# remoteReceive.net
KiCad netlist of a schematic drawn in EAGLE
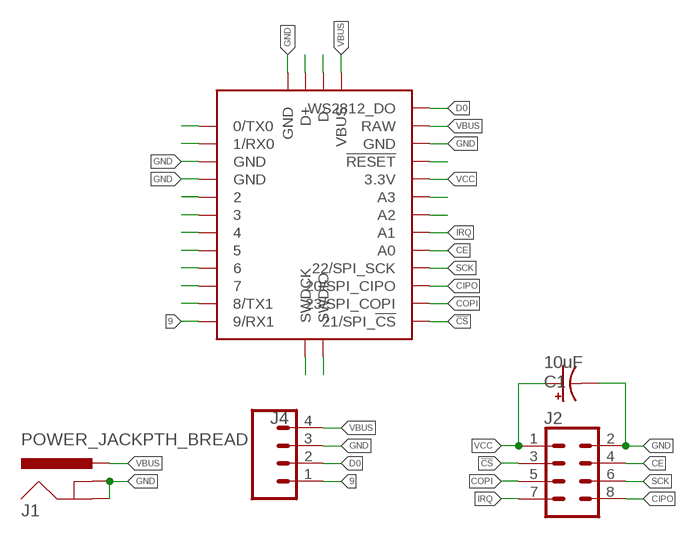
[diagram p0: schematic, sheet 1]

(export (version "E")
  (design (tool "Eeschema 10.0.6"))
  (components
    (comp (ref "C1")
      (value "10uF")
      (footprint "eagle-import:CPOL-RADIAL-2.5MM-5MM-KIT")
      (libsource (lib "eagle-import") (part "10UF-POLAR-RADIAL-2.5MM-KIT-25V-20%"))
    )
    (comp (ref "J1")
      (value "POWER_JACKPTH_BREAD")
      (footprint "eagle-import:POWER_JACK_PTH_BREAD")
      (libsource (lib "eagle-import") (part "POWER_JACKPTH_BREAD"))
    )
    (comp (ref "J2")
      (value "CONN_04X2")
      (footprint "eagle-import:2X4")
      (libsource (lib "eagle-import") (part "CONN_04X2"))
    )
    (comp (ref "J4")
      (value "CONN_04POLAR")
      (footprint "eagle-import:MOLEX-1X4")
      (libsource (lib "eagle-import") (part "CONN_04POLAR"))
    )
    (comp (ref "U$1")
      (value "SF17717_PROMICRORP2040_BREAKOUT")
      (footprint "eagle-import:SF17717_PROMICRORP2040_BREAKOUT")
      (libsource (lib "eagle-import") (part "SF17717_PROMICRORP2040_BREAKOUT"))
    )
  )
  (nets
    (net (code "1") (name "/~{CS}") (class "Default")
      (node (ref "J2") (pin "3") (pinfunction "3_3") (pintype "passive"))
      (node (ref "U$1") (pin "12R") (pinfunction "21/SPI_~{CS}_12R") (pintype "bidirectional"))
      (node (ref "U$1") (pin "12R_PADB") (pinfunction "21/SPI_~{CS}_12R_PADB") (pintype "bidirectional"))
      (node (ref "U$1") (pin "12R_PADT") (pinfunction "21/SPI_~{CS}_12R_PADT") (pintype "bidirectional"))
    )
    (net (code "2") (name "9") (class "Default")
      (node (ref "J4") (pin "1") (pinfunction "1_1") (pintype "passive"))
      (node (ref "U$1") (pin "01L") (pinfunction "9/RX1_01L") (pintype "bidirectional"))
      (node (ref "U$1") (pin "01L_PADB") (pinfunction "9/RX1_01L_PADB") (pintype "bidirectional"))
      (node (ref "U$1") (pin "01L_PADT") (pinfunction "9/RX1_01L_PADT") (pintype "bidirectional"))
    )
    (net (code "3") (name "CE") (class "Default")
      (node (ref "J2") (pin "4") (pinfunction "4_4") (pintype "passive"))
      (node (ref "U$1") (pin "08R") (pinfunction "A0_08R") (pintype "bidirectional"))
      (node (ref "U$1") (pin "08R_PADB") (pinfunction "A0_08R_PADB") (pintype "bidirectional"))
      (node (ref "U$1") (pin "08R_PADT") (pinfunction "A0_08R_PADT") (pintype "bidirectional"))
    )
    (net (code "4") (name "CIPO") (class "Default")
      (node (ref "J2") (pin "8") (pinfunction "8_8") (pintype "passive"))
      (node (ref "U$1") (pin "10R") (pinfunction "20/SPI_CIPO_10R") (pintype "bidirectional"))
      (node (ref "U$1") (pin "10R_PADB") (pinfunction "20/SPI_CIPO_10R_PADB") (pintype "bidirectional"))
      (node (ref "U$1") (pin "10R_PADT") (pinfunction "20/SPI_CIPO_10R_PADT") (pintype "bidirectional"))
    )
    (net (code "5") (name "COPI") (class "Default")
      (node (ref "J2") (pin "5") (pinfunction "5_5") (pintype "passive"))
      (node (ref "U$1") (pin "11R") (pinfunction "23/SPI_COPI_11R") (pintype "bidirectional"))
      (node (ref "U$1") (pin "11R_PADB") (pinfunction "23/SPI_COPI_11R_PADB") (pintype "bidirectional"))
      (node (ref "U$1") (pin "11R_PADT") (pinfunction "23/SPI_COPI_11R_PADT") (pintype "bidirectional"))
    )
    (net (code "6") (name "D0") (class "Default")
      (node (ref "J4") (pin "2") (pinfunction "2_2") (pintype "passive"))
      (node (ref "U$1") (pin "D0_B") (pinfunction "WS2812_DO_D0_B") (pintype "output"))
      (node (ref "U$1") (pin "D0_T") (pinfunction "WS2812_DO_D0_T") (pintype "output"))
    )
    (net (code "7") (name "GND") (class "Default")
      (node (ref "C1") (pin "2") (pinfunction "-_2") (pintype "passive"))
      (node (ref "J1") (pin "GND") (pinfunction "GND_GND") (pintype "bidirectional"))
      (node (ref "J1") (pin "GNDBREAK") (pinfunction "GNDBREAK_GNDBREAK") (pintype "bidirectional"))
      (node (ref "J2") (pin "2") (pinfunction "2_2") (pintype "passive"))
      (node (ref "J4") (pin "3") (pinfunction "3_3") (pintype "passive"))
      (node (ref "U$1") (pin "02R") (pinfunction "GND_02R") (pintype "power_in"))
      (node (ref "U$1") (pin "02R_PADB") (pinfunction "GND_02R_PADB") (pintype "power_in"))
      (node (ref "U$1") (pin "02R_PADT") (pinfunction "GND_02R_PADT") (pintype "power_in"))
      (node (ref "U$1") (pin "09L") (pinfunction "GND_09L") (pintype "power_in"))
      (node (ref "U$1") (pin "09L_PADB") (pinfunction "GND_09L_PADB") (pintype "power_in"))
      (node (ref "U$1") (pin "09L_PADT") (pinfunction "GND_09L_PADT") (pintype "power_in"))
      (node (ref "U$1") (pin "10L") (pinfunction "GND_10L") (pintype "power_in"))
      (node (ref "U$1") (pin "10L_PADB") (pinfunction "GND_10L_PADB") (pintype "power_in"))
      (node (ref "U$1") (pin "10L_PADT") (pinfunction "GND_10L_PADT") (pintype "power_in"))
      (node (ref "U$1") (pin "GND_B") (pinfunction "GND_GND_B") (pintype "power_in"))
      (node (ref "U$1") (pin "GND_T") (pinfunction "GND_GND_T") (pintype "power_in"))
    )
    (net (code "8") (name "IRQ") (class "Default")
      (node (ref "J2") (pin "7") (pinfunction "7_7") (pintype "passive"))
      (node (ref "U$1") (pin "07R") (pinfunction "A1_07R") (pintype "bidirectional"))
      (node (ref "U$1") (pin "07R_PADB") (pinfunction "A1_07R_PADB") (pintype "bidirectional"))
      (node (ref "U$1") (pin "07R_PADT") (pinfunction "A1_07R_PADT") (pintype "bidirectional"))
    )
    (net (code "9") (name "Net-(U$1-0{slash}TX0-Pad12L)") (class "Default")
      (node (ref "U$1") (pin "12L") (pinfunction "0/TX0_12L") (pintype "bidirectional"))
      (node (ref "U$1") (pin "12L_PADB") (pinfunction "0/TX0_12L_PADB") (pintype "bidirectional"))
      (node (ref "U$1") (pin "12L_PADT") (pinfunction "0/TX0_12L_PADT") (pintype "bidirectional"))
    )
    (net (code "10") (name "Net-(U$1-1{slash}RX0-Pad11L)") (class "Default")
      (node (ref "U$1") (pin "11L") (pinfunction "1/RX0_11L") (pintype "bidirectional"))
      (node (ref "U$1") (pin "11L_PADB") (pinfunction "1/RX0_11L_PADB") (pintype "bidirectional"))
      (node (ref "U$1") (pin "11L_PADT") (pinfunction "1/RX0_11L_PADT") (pintype "bidirectional"))
    )
    (net (code "11") (name "Net-(U$1-2-Pad08L)") (class "Default")
      (node (ref "U$1") (pin "08L") (pinfunction "2_08L") (pintype "bidirectional"))
      (node (ref "U$1") (pin "08L_PADB") (pinfunction "2_08L_PADB") (pintype "bidirectional"))
      (node (ref "U$1") (pin "08L_PADT") (pinfunction "2_08L_PADT") (pintype "bidirectional"))
    )
    (net (code "12") (name "Net-(U$1-3-Pad07L)") (class "Default")
      (node (ref "U$1") (pin "07L") (pinfunction "3_07L") (pintype "bidirectional"))
      (node (ref "U$1") (pin "07L_PADB") (pinfunction "3_07L_PADB") (pintype "bidirectional"))
      (node (ref "U$1") (pin "07L_PADT") (pinfunction "3_07L_PADT") (pintype "bidirectional"))
    )
    (net (code "13") (name "Net-(U$1-4-Pad06L)") (class "Default")
      (node (ref "U$1") (pin "06L") (pinfunction "4_06L") (pintype "bidirectional"))
      (node (ref "U$1") (pin "06L_PADB") (pinfunction "4_06L_PADB") (pintype "bidirectional"))
      (node (ref "U$1") (pin "06L_PADT") (pinfunction "4_06L_PADT") (pintype "bidirectional"))
    )
    (net (code "14") (name "Net-(U$1-5-Pad05L)") (class "Default")
      (node (ref "U$1") (pin "05L") (pinfunction "5_05L") (pintype "bidirectional"))
      (node (ref "U$1") (pin "05L_PADB") (pinfunction "5_05L_PADB") (pintype "bidirectional"))
      (node (ref "U$1") (pin "05L_PADT") (pinfunction "5_05L_PADT") (pintype "bidirectional"))
    )
    (net (code "15") (name "Net-(U$1-6-Pad04L)") (class "Default")
      (node (ref "U$1") (pin "04L") (pinfunction "6_04L") (pintype "bidirectional"))
      (node (ref "U$1") (pin "04L_PADB") (pinfunction "6_04L_PADB") (pintype "bidirectional"))
      (node (ref "U$1") (pin "04L_PADT") (pinfunction "6_04L_PADT") (pintype "bidirectional"))
    )
    (net (code "16") (name "Net-(U$1-7-Pad03L)") (class "Default")
      (node (ref "U$1") (pin "03L") (pinfunction "7_03L") (pintype "bidirectional"))
      (node (ref "U$1") (pin "03L_PADB") (pinfunction "7_03L_PADB") (pintype "bidirectional"))
      (node (ref "U$1") (pin "03L_PADT") (pinfunction "7_03L_PADT") (pintype "bidirectional"))
    )
    (net (code "17") (name "Net-(U$1-8{slash}TX1-Pad02L)") (class "Default")
      (node (ref "U$1") (pin "02L") (pinfunction "8/TX1_02L") (pintype "bidirectional"))
      (node (ref "U$1") (pin "02L_PADB") (pinfunction "8/TX1_02L_PADB") (pintype "bidirectional"))
      (node (ref "U$1") (pin "02L_PADT") (pinfunction "8/TX1_02L_PADT") (pintype "bidirectional"))
    )
    (net (code "18") (name "Net-(U$1-A2-Pad06R)") (class "Default")
      (node (ref "U$1") (pin "06R") (pinfunction "A2_06R") (pintype "bidirectional"))
      (node (ref "U$1") (pin "06R_PADB") (pinfunction "A2_06R_PADB") (pintype "bidirectional"))
      (node (ref "U$1") (pin "06R_PADT") (pinfunction "A2_06R_PADT") (pintype "bidirectional"))
    )
    (net (code "19") (name "Net-(U$1-A3-Pad05R)") (class "Default")
      (node (ref "U$1") (pin "05R") (pinfunction "A3_05R") (pintype "bidirectional"))
      (node (ref "U$1") (pin "05R_PADB") (pinfunction "A3_05R_PADB") (pintype "bidirectional"))
      (node (ref "U$1") (pin "05R_PADT") (pinfunction "A3_05R_PADT") (pintype "bidirectional"))
    )
    (net (code "20") (name "Net-(U$1-D+-PadD+_B)") (class "Default")
      (node (ref "U$1") (pin "D+_B") (pinfunction "D+_D+_B") (pintype "bidirectional"))
      (node (ref "U$1") (pin "D+_T") (pinfunction "D+_D+_T") (pintype "bidirectional"))
    )
    (net (code "21") (name "Net-(U$1-D--PadD-_B)") (class "Default")
      (node (ref "U$1") (pin "D-_B") (pinfunction "D-_D-_B") (pintype "bidirectional"))
      (node (ref "U$1") (pin "D-_T") (pinfunction "D-_D-_T") (pintype "bidirectional"))
    )
    (net (code "22") (name "Net-(U$1-SWDCK-PadSWDCK_B)") (class "Default")
      (node (ref "U$1") (pin "SWDCK_B") (pinfunction "SWDCK_SWDCK_B") (pintype "bidirectional"))
      (node (ref "U$1") (pin "SWDCK_T") (pinfunction "SWDCK_SWDCK_T") (pintype "bidirectional"))
    )
    (net (code "23") (name "Net-(U$1-SWDIO-PadSWDIO_B)") (class "Default")
      (node (ref "U$1") (pin "SWDIO_B") (pinfunction "SWDIO_SWDIO_B") (pintype "bidirectional"))
      (node (ref "U$1") (pin "SWDIO_T") (pinfunction "SWDIO_SWDIO_T") (pintype "bidirectional"))
    )
    (net (code "24") (name "Net-(U$1-~{RESET}-Pad03R)") (class "Default")
      (node (ref "U$1") (pin "03R") (pinfunction "~{RESET}_03R") (pintype "power_in"))
      (node (ref "U$1") (pin "03R_PADB") (pinfunction "~{RESET}_03R_PADB") (pintype "power_in"))
      (node (ref "U$1") (pin "03R_PADT") (pinfunction "~{RESET}_03R_PADT") (pintype "power_in"))
    )
    (net (code "25") (name "SCK") (class "Default")
      (node (ref "J2") (pin "6") (pinfunction "6_6") (pintype "passive"))
      (node (ref "U$1") (pin "09R") (pinfunction "22/SPI_SCK_09R") (pintype "bidirectional"))
      (node (ref "U$1") (pin "09R_PADB") (pinfunction "22/SPI_SCK_09R_PADB") (pintype "bidirectional"))
      (node (ref "U$1") (pin "09R_PADT") (pinfunction "22/SPI_SCK_09R_PADT") (pintype "bidirectional"))
    )
    (net (code "26") (name "VBUS") (class "Default")
      (node (ref "J1") (pin "PWR") (pinfunction "PWR_PWR") (pintype "bidirectional"))
      (node (ref "J4") (pin "4") (pinfunction "4_4") (pintype "passive"))
      (node (ref "U$1") (pin "01R") (pinfunction "RAW_01R") (pintype "power_in"))
      (node (ref "U$1") (pin "01R_PADB") (pinfunction "RAW_01R_PADB") (pintype "power_in"))
      (node (ref "U$1") (pin "01R_PADT") (pinfunction "RAW_01R_PADT") (pintype "power_in"))
      (node (ref "U$1") (pin "VBUS_B") (pinfunction "VBUS_VBUS_B") (pintype "power_in"))
      (node (ref "U$1") (pin "VBUS_T") (pinfunction "VBUS_VBUS_T") (pintype "power_in"))
    )
    (net (code "27") (name "VCC") (class "Default")
      (node (ref "C1") (pin "1") (pinfunction "+_1") (pintype "passive"))
      (node (ref "J2") (pin "1") (pinfunction "1_1") (pintype "passive"))
      (node (ref "U$1") (pin "04R") (pinfunction "3.3V_04R") (pintype "bidirectional"))
      (node (ref "U$1") (pin "04R_PADB") (pinfunction "3.3V_04R_PADB") (pintype "bidirectional"))
      (node (ref "U$1") (pin "04R_PADT") (pinfunction "3.3V_04R_PADT") (pintype "bidirectional"))
    )
  )
)
